# Interconnect_board_v1p12.net
KiCad netlist of a schematic drawn in EAGLE
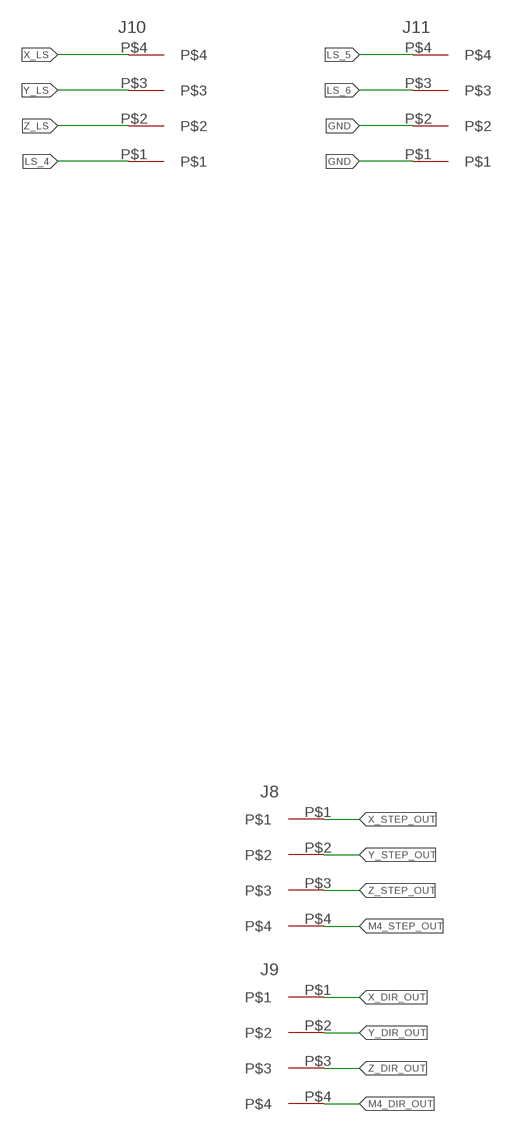
[diagram p0: schematic, sheet 1, part 1 of 2]
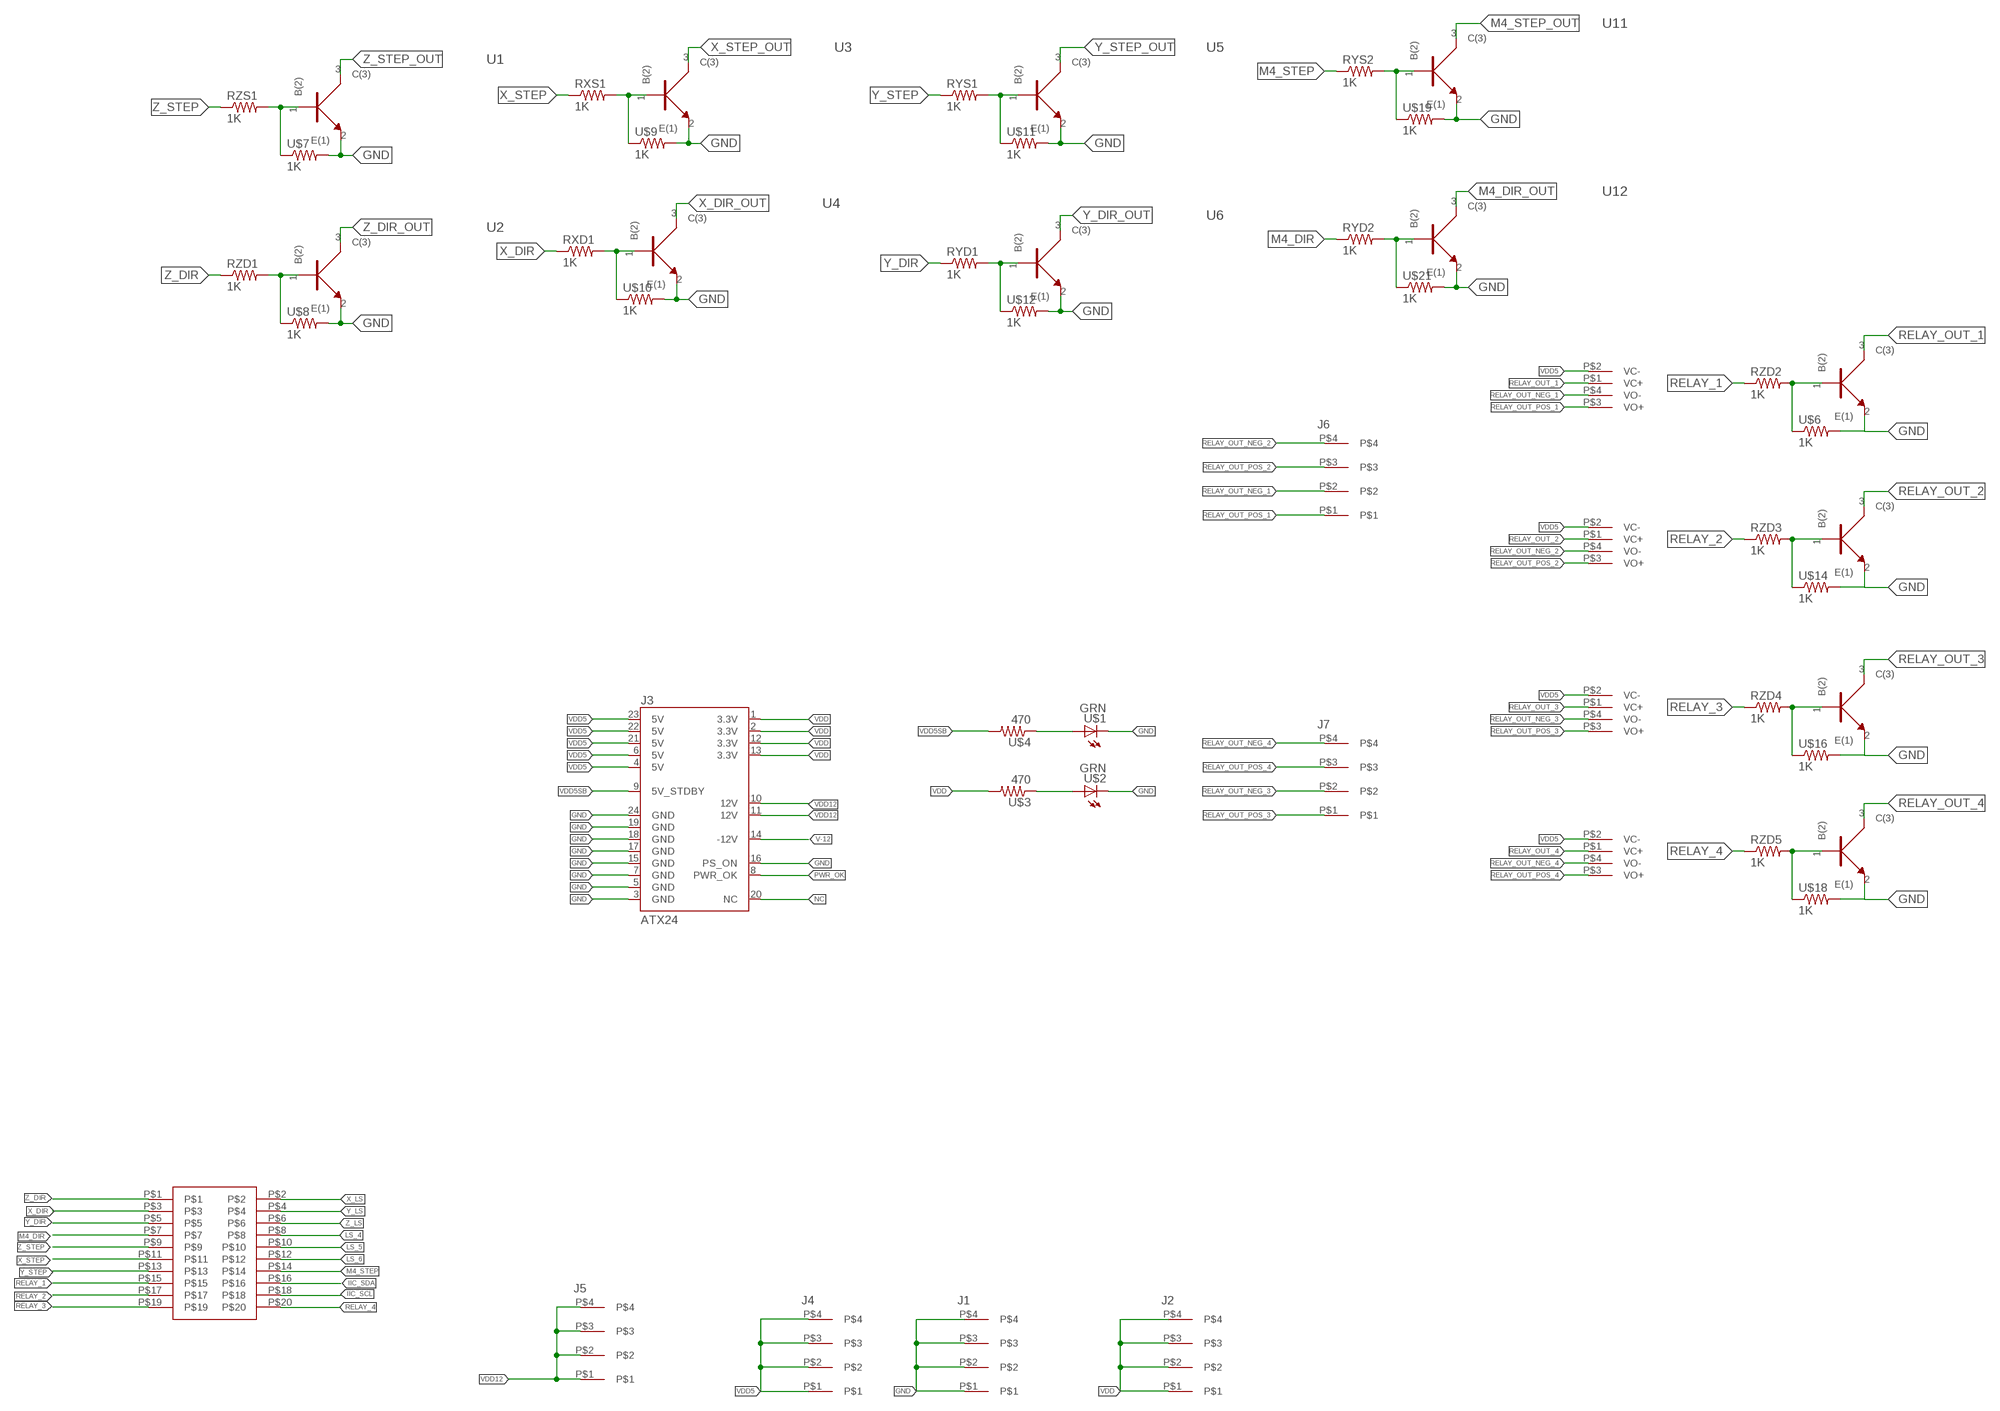
[diagram p1: schematic, sheet 1, part 2 of 2]

(export (version "E")
  (design (tool "Eeschema 10.0.6"))
  (components
    (comp (ref "J1")
      (value "3.81MM_1_X_4_RT_ANGLE_PLUG_HEADER")
      (footprint "eagle-import:1X4_3.81MM_PITCH")
      (libsource (lib "eagle-import") (part "3.81MM_1_X_4_RT_ANGLE_PLUG_HEADER"))
    )
    (comp (ref "J2")
      (value "3.81MM_1_X_4_RT_ANGLE_PLUG_HEADER")
      (footprint "eagle-import:1X4_3.81MM_PITCH")
      (libsource (lib "eagle-import") (part "3.81MM_1_X_4_RT_ANGLE_PLUG_HEADER"))
    )
    (comp (ref "J3")
      (value "ATX24")
      (footprint "eagle-import:ATX24_STRAIGHT")
      (libsource (lib "eagle-import") (part "ATX24"))
    )
    (comp (ref "J4")
      (value "3.81MM_1_X_4_RT_ANGLE_PLUG_HEADER")
      (footprint "eagle-import:1X4_3.81MM_PITCH")
      (libsource (lib "eagle-import") (part "3.81MM_1_X_4_RT_ANGLE_PLUG_HEADER"))
    )
    (comp (ref "J5")
      (value "3.81MM_1_X_4_RT_ANGLE_PLUG_HEADER")
      (footprint "eagle-import:1X4_3.81MM_PITCH")
      (libsource (lib "eagle-import") (part "3.81MM_1_X_4_RT_ANGLE_PLUG_HEADER"))
    )
    (comp (ref "J6")
      (value "3.81MM_1_X_4_RT_ANGLE_PLUG_HEADER")
      (footprint "eagle-import:1X4_3.81MM_PITCH")
      (libsource (lib "eagle-import") (part "3.81MM_1_X_4_RT_ANGLE_PLUG_HEADER"))
    )
    (comp (ref "J7")
      (value "3.81MM_1_X_4_RT_ANGLE_PLUG_HEADER")
      (footprint "eagle-import:1X4_3.81MM_PITCH")
      (libsource (lib "eagle-import") (part "3.81MM_1_X_4_RT_ANGLE_PLUG_HEADER"))
    )
    (comp (ref "J8")
      (value "3.81MM_1_X_4_RT_ANGLE_PLUG_HEADER")
      (footprint "eagle-import:1X4_3.81MM_PITCH")
      (libsource (lib "eagle-import") (part "3.81MM_1_X_4_RT_ANGLE_PLUG_HEADER"))
    )
    (comp (ref "J9")
      (value "3.81MM_1_X_4_RT_ANGLE_PLUG_HEADER")
      (footprint "eagle-import:1X4_3.81MM_PITCH")
      (libsource (lib "eagle-import") (part "3.81MM_1_X_4_RT_ANGLE_PLUG_HEADER"))
    )
    (comp (ref "J10")
      (value "3.81MM_1_X_4_RT_ANGLE_PLUG_HEADER")
      (footprint "eagle-import:1X4_3.81MM_PITCH")
      (libsource (lib "eagle-import") (part "3.81MM_1_X_4_RT_ANGLE_PLUG_HEADER"))
    )
    (comp (ref "J11")
      (value "3.81MM_1_X_4_RT_ANGLE_PLUG_HEADER")
      (footprint "eagle-import:1X4_3.81MM_PITCH")
      (libsource (lib "eagle-import") (part "3.81MM_1_X_4_RT_ANGLE_PLUG_HEADER"))
    )
    (comp (ref "RXD1")
      (value "R_0805_1K")
      (footprint "eagle-import:R_0805_1K")
      (libsource (lib "eagle-import") (part "R_0805_1K"))
    )
    (comp (ref "RXS1")
      (value "R_0805_1K")
      (footprint "eagle-import:R_0805_1K")
      (libsource (lib "eagle-import") (part "R_0805_1K"))
    )
    (comp (ref "RYD1")
      (value "R_0805_1K")
      (footprint "eagle-import:R_0805_1K")
      (libsource (lib "eagle-import") (part "R_0805_1K"))
    )
    (comp (ref "RYD2")
      (value "R_0805_1K")
      (footprint "eagle-import:R_0805_1K")
      (libsource (lib "eagle-import") (part "R_0805_1K"))
    )
    (comp (ref "RYS1")
      (value "R_0805_1K")
      (footprint "eagle-import:R_0805_1K")
      (libsource (lib "eagle-import") (part "R_0805_1K"))
    )
    (comp (ref "RYS2")
      (value "R_0805_1K")
      (footprint "eagle-import:R_0805_1K")
      (libsource (lib "eagle-import") (part "R_0805_1K"))
    )
    (comp (ref "RZD1")
      (value "R_0805_1K")
      (footprint "eagle-import:R_0805_1K")
      (libsource (lib "eagle-import") (part "R_0805_1K"))
    )
    (comp (ref "RZD2")
      (value "R_0805_1K")
      (footprint "eagle-import:R_0805_1K")
      (libsource (lib "eagle-import") (part "R_0805_1K"))
    )
    (comp (ref "RZD3")
      (value "R_0805_1K")
      (footprint "eagle-import:R_0805_1K")
      (libsource (lib "eagle-import") (part "R_0805_1K"))
    )
    (comp (ref "RZD4")
      (value "R_0805_1K")
      (footprint "eagle-import:R_0805_1K")
      (libsource (lib "eagle-import") (part "R_0805_1K"))
    )
    (comp (ref "RZD5")
      (value "R_0805_1K")
      (footprint "eagle-import:R_0805_1K")
      (libsource (lib "eagle-import") (part "R_0805_1K"))
    )
    (comp (ref "RZS1")
      (value "R_0805_1K")
      (footprint "eagle-import:R_0805_1K")
      (libsource (lib "eagle-import") (part "R_0805_1K"))
    )
    (comp (ref "U$1")
      (value "LED_0805_GREEN")
      (footprint "eagle-import:LED_0805_GREEN")
      (libsource (lib "eagle-import") (part "LED_0805_GREEN"))
    )
    (comp (ref "U$2")
      (value "LED_0805_GREEN")
      (footprint "eagle-import:LED_0805_GREEN")
      (libsource (lib "eagle-import") (part "LED_0805_GREEN"))
    )
    (comp (ref "U$3")
      (value "R_0805_470")
      (footprint "eagle-import:R_0805_470")
      (libsource (lib "eagle-import") (part "R_0805_470"))
    )
    (comp (ref "U$4")
      (value "R_0805_470")
      (footprint "eagle-import:R_0805_470")
      (libsource (lib "eagle-import") (part "R_0805_470"))
    )
    (comp (ref "U$5")
      (value "RELAY_KYOTO_KF0604D")
      (footprint "eagle-import:RELAY_KYOTO_KF0604D")
      (libsource (lib "eagle-import") (part "RELAY_KYOTO_KF0604D"))
    )
    (comp (ref "U$6")
      (value "R_0805_1K")
      (footprint "eagle-import:R_0805_1K")
      (libsource (lib "eagle-import") (part "R_0805_1K"))
    )
    (comp (ref "U$7")
      (value "R_0805_1K")
      (footprint "eagle-import:R_0805_1K")
      (libsource (lib "eagle-import") (part "R_0805_1K"))
    )
    (comp (ref "U$8")
      (value "R_0805_1K")
      (footprint "eagle-import:R_0805_1K")
      (libsource (lib "eagle-import") (part "R_0805_1K"))
    )
    (comp (ref "U$9")
      (value "R_0805_1K")
      (footprint "eagle-import:R_0805_1K")
      (libsource (lib "eagle-import") (part "R_0805_1K"))
    )
    (comp (ref "U$10")
      (value "R_0805_1K")
      (footprint "eagle-import:R_0805_1K")
      (libsource (lib "eagle-import") (part "R_0805_1K"))
    )
    (comp (ref "U$11")
      (value "R_0805_1K")
      (footprint "eagle-import:R_0805_1K")
      (libsource (lib "eagle-import") (part "R_0805_1K"))
    )
    (comp (ref "U$12")
      (value "R_0805_1K")
      (footprint "eagle-import:R_0805_1K")
      (libsource (lib "eagle-import") (part "R_0805_1K"))
    )
    (comp (ref "U$13")
      (value "RELAY_KYOTO_KF0604D")
      (footprint "eagle-import:RELAY_KYOTO_KF0604D")
      (libsource (lib "eagle-import") (part "RELAY_KYOTO_KF0604D"))
    )
    (comp (ref "U$14")
      (value "R_0805_1K")
      (footprint "eagle-import:R_0805_1K")
      (libsource (lib "eagle-import") (part "R_0805_1K"))
    )
    (comp (ref "U$15")
      (value "RELAY_KYOTO_KF0604D")
      (footprint "eagle-import:RELAY_KYOTO_KF0604D")
      (libsource (lib "eagle-import") (part "RELAY_KYOTO_KF0604D"))
    )
    (comp (ref "U$16")
      (value "R_0805_1K")
      (footprint "eagle-import:R_0805_1K")
      (libsource (lib "eagle-import") (part "R_0805_1K"))
    )
    (comp (ref "U$17")
      (value "RELAY_KYOTO_KF0604D")
      (footprint "eagle-import:RELAY_KYOTO_KF0604D")
      (libsource (lib "eagle-import") (part "RELAY_KYOTO_KF0604D"))
    )
    (comp (ref "U$18")
      (value "R_0805_1K")
      (footprint "eagle-import:R_0805_1K")
      (libsource (lib "eagle-import") (part "R_0805_1K"))
    )
    (comp (ref "U$19")
      (value "R_0805_1K")
      (footprint "eagle-import:R_0805_1K")
      (libsource (lib "eagle-import") (part "R_0805_1K"))
    )
    (comp (ref "U$21")
      (value "R_0805_1K")
      (footprint "eagle-import:R_0805_1K")
      (libsource (lib "eagle-import") (part "R_0805_1K"))
    )
    (comp (ref "U$26")
      (value "2_X_10_HEADER_GENERIC")
      (footprint "eagle-import:2_X_10_.1_INCH")
      (libsource (lib "eagle-import") (part "2_X_10_HEADER_GENERIC"))
    )
    (comp (ref "U1")
      (value "BC846BW")
      (footprint "eagle-import:SOT323")
      (libsource (lib "eagle-import") (part "BC846BW"))
    )
    (comp (ref "U2")
      (value "BC846BW")
      (footprint "eagle-import:SOT323")
      (libsource (lib "eagle-import") (part "BC846BW"))
    )
    (comp (ref "U3")
      (value "BC846BW")
      (footprint "eagle-import:SOT323")
      (libsource (lib "eagle-import") (part "BC846BW"))
    )
    (comp (ref "U4")
      (value "BC846BW")
      (footprint "eagle-import:SOT323")
      (libsource (lib "eagle-import") (part "BC846BW"))
    )
    (comp (ref "U5")
      (value "BC846BW")
      (footprint "eagle-import:SOT323")
      (libsource (lib "eagle-import") (part "BC846BW"))
    )
    (comp (ref "U6")
      (value "BC846BW")
      (footprint "eagle-import:SOT323")
      (libsource (lib "eagle-import") (part "BC846BW"))
    )
    (comp (ref "U7")
      (value "BC846BW")
      (footprint "eagle-import:SOT323")
      (libsource (lib "eagle-import") (part "BC846BW"))
    )
    (comp (ref "U8")
      (value "BC846BW")
      (footprint "eagle-import:SOT323")
      (libsource (lib "eagle-import") (part "BC846BW"))
    )
    (comp (ref "U9")
      (value "BC846BW")
      (footprint "eagle-import:SOT323")
      (libsource (lib "eagle-import") (part "BC846BW"))
    )
    (comp (ref "U10")
      (value "BC846BW")
      (footprint "eagle-import:SOT323")
      (libsource (lib "eagle-import") (part "BC846BW"))
    )
    (comp (ref "U11")
      (value "BC846BW")
      (footprint "eagle-import:SOT323")
      (libsource (lib "eagle-import") (part "BC846BW"))
    )
    (comp (ref "U12")
      (value "BC846BW")
      (footprint "eagle-import:SOT323")
      (libsource (lib "eagle-import") (part "BC846BW"))
    )
  )
  (nets
    (net (code "1") (name "GND") (class "Default")
      (node (ref "J1") (pin "P$1") (pinfunction "P$1_P$1") (pintype "bidirectional"))
      (node (ref "J1") (pin "P$2") (pinfunction "P$2_P$2") (pintype "bidirectional"))
      (node (ref "J1") (pin "P$3") (pinfunction "P$3_P$3") (pintype "bidirectional"))
      (node (ref "J1") (pin "P$4") (pinfunction "P$4_P$4") (pintype "bidirectional"))
      (node (ref "J11") (pin "P$1") (pinfunction "P$1_P$1") (pintype "bidirectional"))
      (node (ref "J11") (pin "P$2") (pinfunction "P$2_P$2") (pintype "bidirectional"))
      (node (ref "J3") (pin "15") (pinfunction "GND_15") (pintype "bidirectional"))
      (node (ref "J3") (pin "16") (pinfunction "PS_ON_16") (pintype "bidirectional"))
      (node (ref "J3") (pin "17") (pinfunction "GND_17") (pintype "bidirectional"))
      (node (ref "J3") (pin "18") (pinfunction "GND_18") (pintype "bidirectional"))
      (node (ref "J3") (pin "19") (pinfunction "GND_19") (pintype "bidirectional"))
      (node (ref "J3") (pin "24") (pinfunction "GND_24") (pintype "bidirectional"))
      (node (ref "J3") (pin "3") (pinfunction "GND_3") (pintype "bidirectional"))
      (node (ref "J3") (pin "5") (pinfunction "GND_5") (pintype "bidirectional"))
      (node (ref "J3") (pin "7") (pinfunction "GND_7") (pintype "bidirectional"))
      (node (ref "U$1") (pin "C") (pinfunction "C_C") (pintype "passive"))
      (node (ref "U$10") (pin "2") (pinfunction "2_2") (pintype "passive"))
      (node (ref "U$11") (pin "2") (pinfunction "2_2") (pintype "passive"))
      (node (ref "U$12") (pin "2") (pinfunction "2_2") (pintype "passive"))
      (node (ref "U$14") (pin "2") (pinfunction "2_2") (pintype "passive"))
      (node (ref "U$16") (pin "2") (pinfunction "2_2") (pintype "passive"))
      (node (ref "U$18") (pin "2") (pinfunction "2_2") (pintype "passive"))
      (node (ref "U$19") (pin "2") (pinfunction "2_2") (pintype "passive"))
      (node (ref "U$2") (pin "C") (pinfunction "C_C") (pintype "passive"))
      (node (ref "U$21") (pin "2") (pinfunction "2_2") (pintype "passive"))
      (node (ref "U$6") (pin "2") (pinfunction "2_2") (pintype "passive"))
      (node (ref "U$7") (pin "2") (pinfunction "2_2") (pintype "passive"))
      (node (ref "U$8") (pin "2") (pinfunction "2_2") (pintype "passive"))
      (node (ref "U$9") (pin "2") (pinfunction "2_2") (pintype "passive"))
      (node (ref "U1") (pin "2") (pinfunction "E(1)_2") (pintype "output"))
      (node (ref "U10") (pin "2") (pinfunction "E(1)_2") (pintype "output"))
      (node (ref "U11") (pin "2") (pinfunction "E(1)_2") (pintype "output"))
      (node (ref "U12") (pin "2") (pinfunction "E(1)_2") (pintype "output"))
      (node (ref "U2") (pin "2") (pinfunction "E(1)_2") (pintype "output"))
      (node (ref "U3") (pin "2") (pinfunction "E(1)_2") (pintype "output"))
      (node (ref "U4") (pin "2") (pinfunction "E(1)_2") (pintype "output"))
      (node (ref "U5") (pin "2") (pinfunction "E(1)_2") (pintype "output"))
      (node (ref "U6") (pin "2") (pinfunction "E(1)_2") (pintype "output"))
      (node (ref "U7") (pin "2") (pinfunction "E(1)_2") (pintype "output"))
      (node (ref "U8") (pin "2") (pinfunction "E(1)_2") (pintype "output"))
      (node (ref "U9") (pin "2") (pinfunction "E(1)_2") (pintype "output"))
    )
    (net (code "2") (name "IIC_SCL") (class "Default")
      (node (ref "U$26") (pin "P$18") (pinfunction "P$18_P$18") (pintype "bidirectional"))
    )
    (net (code "3") (name "IIC_SDA") (class "Default")
      (node (ref "U$26") (pin "P$16") (pinfunction "P$16_P$16") (pintype "bidirectional"))
    )
    (net (code "4") (name "LS_4") (class "Default")
      (node (ref "J10") (pin "P$1") (pinfunction "P$1_P$1") (pintype "bidirectional"))
      (node (ref "U$26") (pin "P$8") (pinfunction "P$8_P$8") (pintype "bidirectional"))
    )
    (net (code "5") (name "LS_5") (class "Default")
      (node (ref "J11") (pin "P$4") (pinfunction "P$4_P$4") (pintype "bidirectional"))
      (node (ref "U$26") (pin "P$10") (pinfunction "P$10_P$10") (pintype "bidirectional"))
    )
    (net (code "6") (name "LS_6") (class "Default")
      (node (ref "J11") (pin "P$3") (pinfunction "P$3_P$3") (pintype "bidirectional"))
      (node (ref "U$26") (pin "P$12") (pinfunction "P$12_P$12") (pintype "bidirectional"))
    )
    (net (code "7") (name "M4_DIR") (class "Default")
      (node (ref "RYD2") (pin "1") (pinfunction "1_1") (pintype "passive"))
      (node (ref "U$26") (pin "P$7") (pinfunction "P$7_P$7") (pintype "bidirectional"))
    )
    (net (code "8") (name "M4_DIR_OUT") (class "Default")
      (node (ref "J9") (pin "P$4") (pinfunction "P$4_P$4") (pintype "bidirectional"))
      (node (ref "U12") (pin "3") (pinfunction "C(3)_3") (pintype "input"))
    )
    (net (code "9") (name "M4_STEP") (class "Default")
      (node (ref "RYS2") (pin "1") (pinfunction "1_1") (pintype "passive"))
      (node (ref "U$26") (pin "P$14") (pinfunction "P$14_P$14") (pintype "bidirectional"))
    )
    (net (code "10") (name "M4_STEP_OUT") (class "Default")
      (node (ref "J8") (pin "P$4") (pinfunction "P$4_P$4") (pintype "bidirectional"))
      (node (ref "U11") (pin "3") (pinfunction "C(3)_3") (pintype "input"))
    )
    (net (code "11") (name "NC") (class "Default")
      (node (ref "J3") (pin "20") (pinfunction "NC_20") (pintype "bidirectional"))
    )
    (net (code "12") (name "Net-(U$1-PadA)") (class "Default")
      (node (ref "U$1") (pin "A") (pinfunction "A_A") (pintype "passive"))
      (node (ref "U$4") (pin "1") (pinfunction "1_1") (pintype "passive"))
    )
    (net (code "13") (name "Net-(U$2-PadA)") (class "Default")
      (node (ref "U$2") (pin "A") (pinfunction "A_A") (pintype "passive"))
      (node (ref "U$3") (pin "1") (pinfunction "1_1") (pintype "passive"))
    )
    (net (code "14") (name "Net-(U1-B(2))") (class "Default")
      (node (ref "RZS1") (pin "2") (pinfunction "2_2") (pintype "passive"))
      (node (ref "U$7") (pin "1") (pinfunction "1_1") (pintype "passive"))
      (node (ref "U1") (pin "1") (pinfunction "B(2)_1") (pintype "input"))
    )
    (net (code "15") (name "Net-(U2-B(2))") (class "Default")
      (node (ref "RZD1") (pin "2") (pinfunction "2_2") (pintype "passive"))
      (node (ref "U$8") (pin "1") (pinfunction "1_1") (pintype "passive"))
      (node (ref "U2") (pin "1") (pinfunction "B(2)_1") (pintype "input"))
    )
    (net (code "16") (name "Net-(U3-B(2))") (class "Default")
      (node (ref "RXS1") (pin "2") (pinfunction "2_2") (pintype "passive"))
      (node (ref "U$9") (pin "1") (pinfunction "1_1") (pintype "passive"))
      (node (ref "U3") (pin "1") (pinfunction "B(2)_1") (pintype "input"))
    )
    (net (code "17") (name "Net-(U4-B(2))") (class "Default")
      (node (ref "RXD1") (pin "2") (pinfunction "2_2") (pintype "passive"))
      (node (ref "U$10") (pin "1") (pinfunction "1_1") (pintype "passive"))
      (node (ref "U4") (pin "1") (pinfunction "B(2)_1") (pintype "input"))
    )
    (net (code "18") (name "Net-(U5-B(2))") (class "Default")
      (node (ref "RYS1") (pin "2") (pinfunction "2_2") (pintype "passive"))
      (node (ref "U$11") (pin "1") (pinfunction "1_1") (pintype "passive"))
      (node (ref "U5") (pin "1") (pinfunction "B(2)_1") (pintype "input"))
    )
    (net (code "19") (name "Net-(U6-B(2))") (class "Default")
      (node (ref "RYD1") (pin "2") (pinfunction "2_2") (pintype "passive"))
      (node (ref "U$12") (pin "1") (pinfunction "1_1") (pintype "passive"))
      (node (ref "U6") (pin "1") (pinfunction "B(2)_1") (pintype "input"))
    )
    (net (code "20") (name "Net-(U7-B(2))") (class "Default")
      (node (ref "RZD2") (pin "2") (pinfunction "2_2") (pintype "passive"))
      (node (ref "U$6") (pin "1") (pinfunction "1_1") (pintype "passive"))
      (node (ref "U7") (pin "1") (pinfunction "B(2)_1") (pintype "input"))
    )
    (net (code "21") (name "Net-(U8-B(2))") (class "Default")
      (node (ref "RZD3") (pin "2") (pinfunction "2_2") (pintype "passive"))
      (node (ref "U$14") (pin "1") (pinfunction "1_1") (pintype "passive"))
      (node (ref "U8") (pin "1") (pinfunction "B(2)_1") (pintype "input"))
    )
    (net (code "22") (name "Net-(U9-B(2))") (class "Default")
      (node (ref "RZD4") (pin "2") (pinfunction "2_2") (pintype "passive"))
      (node (ref "U$16") (pin "1") (pinfunction "1_1") (pintype "passive"))
      (node (ref "U9") (pin "1") (pinfunction "B(2)_1") (pintype "input"))
    )
    (net (code "23") (name "Net-(U10-B(2))") (class "Default")
      (node (ref "RZD5") (pin "2") (pinfunction "2_2") (pintype "passive"))
      (node (ref "U$18") (pin "1") (pinfunction "1_1") (pintype "passive"))
      (node (ref "U10") (pin "1") (pinfunction "B(2)_1") (pintype "input"))
    )
    (net (code "24") (name "Net-(U11-B(2))") (class "Default")
      (node (ref "RYS2") (pin "2") (pinfunction "2_2") (pintype "passive"))
      (node (ref "U$19") (pin "1") (pinfunction "1_1") (pintype "passive"))
      (node (ref "U11") (pin "1") (pinfunction "B(2)_1") (pintype "input"))
    )
    (net (code "25") (name "Net-(U12-B(2))") (class "Default")
      (node (ref "RYD2") (pin "2") (pinfunction "2_2") (pintype "passive"))
      (node (ref "U$21") (pin "1") (pinfunction "1_1") (pintype "passive"))
      (node (ref "U12") (pin "1") (pinfunction "B(2)_1") (pintype "input"))
    )
    (net (code "26") (name "PWR_OK") (class "Default")
      (node (ref "J3") (pin "8") (pinfunction "PWR_OK_8") (pintype "bidirectional"))
    )
    (net (code "27") (name "RELAY_1") (class "Default")
      (node (ref "RZD2") (pin "1") (pinfunction "1_1") (pintype "passive"))
      (node (ref "U$26") (pin "P$15") (pinfunction "P$15_P$15") (pintype "bidirectional"))
    )
    (net (code "28") (name "RELAY_2") (class "Default")
      (node (ref "RZD3") (pin "1") (pinfunction "1_1") (pintype "passive"))
      (node (ref "U$26") (pin "P$17") (pinfunction "P$17_P$17") (pintype "bidirectional"))
    )
    (net (code "29") (name "RELAY_3") (class "Default")
      (node (ref "RZD4") (pin "1") (pinfunction "1_1") (pintype "passive"))
      (node (ref "U$26") (pin "P$19") (pinfunction "P$19_P$19") (pintype "bidirectional"))
    )
    (net (code "30") (name "RELAY_4") (class "Default")
      (node (ref "RZD5") (pin "1") (pinfunction "1_1") (pintype "passive"))
      (node (ref "U$26") (pin "P$20") (pinfunction "P$20_P$20") (pintype "bidirectional"))
    )
    (net (code "31") (name "RELAY_OUT_1") (class "Default")
      (node (ref "U$5") (pin "P$1") (pinfunction "VC+_P$1") (pintype "bidirectional"))
      (node (ref "U7") (pin "3") (pinfunction "C(3)_3") (pintype "input"))
    )
    (net (code "32") (name "RELAY_OUT_2") (class "Default")
      (node (ref "U$13") (pin "P$1") (pinfunction "VC+_P$1") (pintype "bidirectional"))
      (node (ref "U8") (pin "3") (pinfunction "C(3)_3") (pintype "input"))
    )
    (net (code "33") (name "RELAY_OUT_3") (class "Default")
      (node (ref "U$15") (pin "P$1") (pinfunction "VC+_P$1") (pintype "bidirectional"))
      (node (ref "U9") (pin "3") (pinfunction "C(3)_3") (pintype "input"))
    )
    (net (code "34") (name "RELAY_OUT_4") (class "Default")
      (node (ref "U$17") (pin "P$1") (pinfunction "VC+_P$1") (pintype "bidirectional"))
      (node (ref "U10") (pin "3") (pinfunction "C(3)_3") (pintype "input"))
    )
    (net (code "35") (name "RELAY_OUT_NEG_1") (class "Default")
      (node (ref "J6") (pin "P$2") (pinfunction "P$2_P$2") (pintype "bidirectional"))
      (node (ref "U$5") (pin "P$4") (pinfunction "VO-_P$4") (pintype "bidirectional"))
    )
    (net (code "36") (name "RELAY_OUT_NEG_2") (class "Default")
      (node (ref "J6") (pin "P$4") (pinfunction "P$4_P$4") (pintype "bidirectional"))
      (node (ref "U$13") (pin "P$4") (pinfunction "VO-_P$4") (pintype "bidirectional"))
    )
    (net (code "37") (name "RELAY_OUT_NEG_3") (class "Default")
      (node (ref "J7") (pin "P$2") (pinfunction "P$2_P$2") (pintype "bidirectional"))
      (node (ref "U$15") (pin "P$4") (pinfunction "VO-_P$4") (pintype "bidirectional"))
    )
    (net (code "38") (name "RELAY_OUT_NEG_4") (class "Default")
      (node (ref "J7") (pin "P$4") (pinfunction "P$4_P$4") (pintype "bidirectional"))
      (node (ref "U$17") (pin "P$4") (pinfunction "VO-_P$4") (pintype "bidirectional"))
    )
    (net (code "39") (name "RELAY_OUT_POS_1") (class "Default")
      (node (ref "J6") (pin "P$1") (pinfunction "P$1_P$1") (pintype "bidirectional"))
      (node (ref "U$5") (pin "P$3") (pinfunction "VO+_P$3") (pintype "bidirectional"))
    )
    (net (code "40") (name "RELAY_OUT_POS_2") (class "Default")
      (node (ref "J6") (pin "P$3") (pinfunction "P$3_P$3") (pintype "bidirectional"))
      (node (ref "U$13") (pin "P$3") (pinfunction "VO+_P$3") (pintype "bidirectional"))
    )
    (net (code "41") (name "RELAY_OUT_POS_3") (class "Default")
      (node (ref "J7") (pin "P$1") (pinfunction "P$1_P$1") (pintype "bidirectional"))
      (node (ref "U$15") (pin "P$3") (pinfunction "VO+_P$3") (pintype "bidirectional"))
    )
    (net (code "42") (name "RELAY_OUT_POS_4") (class "Default")
      (node (ref "J7") (pin "P$3") (pinfunction "P$3_P$3") (pintype "bidirectional"))
      (node (ref "U$17") (pin "P$3") (pinfunction "VO+_P$3") (pintype "bidirectional"))
    )
    (net (code "43") (name "V-12") (class "Default")
      (node (ref "J3") (pin "14") (pinfunction "-12V_14") (pintype "bidirectional"))
    )
    (net (code "44") (name "VDD") (class "Default")
      (node (ref "J2") (pin "P$1") (pinfunction "P$1_P$1") (pintype "bidirectional"))
      (node (ref "J2") (pin "P$2") (pinfunction "P$2_P$2") (pintype "bidirectional"))
      (node (ref "J2") (pin "P$3") (pinfunction "P$3_P$3") (pintype "bidirectional"))
      (node (ref "J2") (pin "P$4") (pinfunction "P$4_P$4") (pintype "bidirectional"))
      (node (ref "J3") (pin "1") (pinfunction "3.3V_1") (pintype "bidirectional"))
      (node (ref "J3") (pin "12") (pinfunction "3.3V_12") (pintype "bidirectional"))
      (node (ref "J3") (pin "13") (pinfunction "3.3V_13") (pintype "bidirectional"))
      (node (ref "J3") (pin "2") (pinfunction "3.3V_2") (pintype "bidirectional"))
      (node (ref "U$3") (pin "2") (pinfunction "2_2") (pintype "passive"))
    )
    (net (code "45") (name "VDD5") (class "Default")
      (node (ref "J3") (pin "21") (pinfunction "5V_21") (pintype "bidirectional"))
      (node (ref "J3") (pin "22") (pinfunction "5V_22") (pintype "bidirectional"))
      (node (ref "J3") (pin "23") (pinfunction "5V_23") (pintype "bidirectional"))
      (node (ref "J3") (pin "4") (pinfunction "5V_4") (pintype "bidirectional"))
      (node (ref "J3") (pin "6") (pinfunction "5V_6") (pintype "bidirectional"))
      (node (ref "J4") (pin "P$1") (pinfunction "P$1_P$1") (pintype "bidirectional"))
      (node (ref "J4") (pin "P$2") (pinfunction "P$2_P$2") (pintype "bidirectional"))
      (node (ref "J4") (pin "P$3") (pinfunction "P$3_P$3") (pintype "bidirectional"))
      (node (ref "J4") (pin "P$4") (pinfunction "P$4_P$4") (pintype "bidirectional"))
      (node (ref "U$13") (pin "P$2") (pinfunction "VC-_P$2") (pintype "bidirectional"))
      (node (ref "U$15") (pin "P$2") (pinfunction "VC-_P$2") (pintype "bidirectional"))
      (node (ref "U$17") (pin "P$2") (pinfunction "VC-_P$2") (pintype "bidirectional"))
      (node (ref "U$5") (pin "P$2") (pinfunction "VC-_P$2") (pintype "bidirectional"))
    )
    (net (code "46") (name "VDD5SB") (class "Default")
      (node (ref "J3") (pin "9") (pinfunction "5V_STDBY_9") (pintype "bidirectional"))
      (node (ref "U$4") (pin "2") (pinfunction "2_2") (pintype "passive"))
    )
    (net (code "47") (name "VDD12") (class "Default")
      (node (ref "J3") (pin "10") (pinfunction "12V_10") (pintype "bidirectional"))
      (node (ref "J3") (pin "11") (pinfunction "12V_11") (pintype "bidirectional"))
      (node (ref "J5") (pin "P$1") (pinfunction "P$1_P$1") (pintype "bidirectional"))
      (node (ref "J5") (pin "P$2") (pinfunction "P$2_P$2") (pintype "bidirectional"))
      (node (ref "J5") (pin "P$3") (pinfunction "P$3_P$3") (pintype "bidirectional"))
      (node (ref "J5") (pin "P$4") (pinfunction "P$4_P$4") (pintype "bidirectional"))
    )
    (net (code "48") (name "X_DIR") (class "Default")
      (node (ref "RXD1") (pin "1") (pinfunction "1_1") (pintype "passive"))
      (node (ref "U$26") (pin "P$3") (pinfunction "P$3_P$3") (pintype "bidirectional"))
    )
    (net (code "49") (name "X_DIR_OUT") (class "Default")
      (node (ref "J9") (pin "P$1") (pinfunction "P$1_P$1") (pintype "bidirectional"))
      (node (ref "U4") (pin "3") (pinfunction "C(3)_3") (pintype "input"))
    )
    (net (code "50") (name "X_LS") (class "Default")
      (node (ref "J10") (pin "P$4") (pinfunction "P$4_P$4") (pintype "bidirectional"))
      (node (ref "U$26") (pin "P$2") (pinfunction "P$2_P$2") (pintype "bidirectional"))
    )
    (net (code "51") (name "X_STEP") (class "Default")
      (node (ref "RXS1") (pin "1") (pinfunction "1_1") (pintype "passive"))
      (node (ref "U$26") (pin "P$11") (pinfunction "P$11_P$11") (pintype "bidirectional"))
    )
    (net (code "52") (name "X_STEP_OUT") (class "Default")
      (node (ref "J8") (pin "P$1") (pinfunction "P$1_P$1") (pintype "bidirectional"))
      (node (ref "U3") (pin "3") (pinfunction "C(3)_3") (pintype "input"))
    )
    (net (code "53") (name "Y_DIR") (class "Default")
      (node (ref "RYD1") (pin "1") (pinfunction "1_1") (pintype "passive"))
      (node (ref "U$26") (pin "P$5") (pinfunction "P$5_P$5") (pintype "bidirectional"))
    )
    (net (code "54") (name "Y_DIR_OUT") (class "Default")
      (node (ref "J9") (pin "P$2") (pinfunction "P$2_P$2") (pintype "bidirectional"))
      (node (ref "U6") (pin "3") (pinfunction "C(3)_3") (pintype "input"))
    )
    (net (code "55") (name "Y_LS") (class "Default")
      (node (ref "J10") (pin "P$3") (pinfunction "P$3_P$3") (pintype "bidirectional"))
      (node (ref "U$26") (pin "P$4") (pinfunction "P$4_P$4") (pintype "bidirectional"))
    )
    (net (code "56") (name "Y_STEP") (class "Default")
      (node (ref "RYS1") (pin "1") (pinfunction "1_1") (pintype "passive"))
      (node (ref "U$26") (pin "P$13") (pinfunction "P$13_P$13") (pintype "bidirectional"))
    )
    (net (code "57") (name "Y_STEP_OUT") (class "Default")
      (node (ref "J8") (pin "P$2") (pinfunction "P$2_P$2") (pintype "bidirectional"))
      (node (ref "U5") (pin "3") (pinfunction "C(3)_3") (pintype "input"))
    )
    (net (code "58") (name "Z_DIR") (class "Default")
      (node (ref "RZD1") (pin "1") (pinfunction "1_1") (pintype "passive"))
      (node (ref "U$26") (pin "P$1") (pinfunction "P$1_P$1") (pintype "bidirectional"))
    )
    (net (code "59") (name "Z_DIR_OUT") (class "Default")
      (node (ref "J9") (pin "P$3") (pinfunction "P$3_P$3") (pintype "bidirectional"))
      (node (ref "U2") (pin "3") (pinfunction "C(3)_3") (pintype "input"))
    )
    (net (code "60") (name "Z_LS") (class "Default")
      (node (ref "J10") (pin "P$2") (pinfunction "P$2_P$2") (pintype "bidirectional"))
      (node (ref "U$26") (pin "P$6") (pinfunction "P$6_P$6") (pintype "bidirectional"))
    )
    (net (code "61") (name "Z_STEP") (class "Default")
      (node (ref "RZS1") (pin "1") (pinfunction "1_1") (pintype "passive"))
      (node (ref "U$26") (pin "P$9") (pinfunction "P$9_P$9") (pintype "bidirectional"))
    )
    (net (code "62") (name "Z_STEP_OUT") (class "Default")
      (node (ref "J8") (pin "P$3") (pinfunction "P$3_P$3") (pintype "bidirectional"))
      (node (ref "U1") (pin "3") (pinfunction "C(3)_3") (pintype "input"))
    )
  )
)
